# SparkFun_Mono_Audio_Amp-TPA2005D1.net
KiCad netlist of a schematic drawn in EAGLE
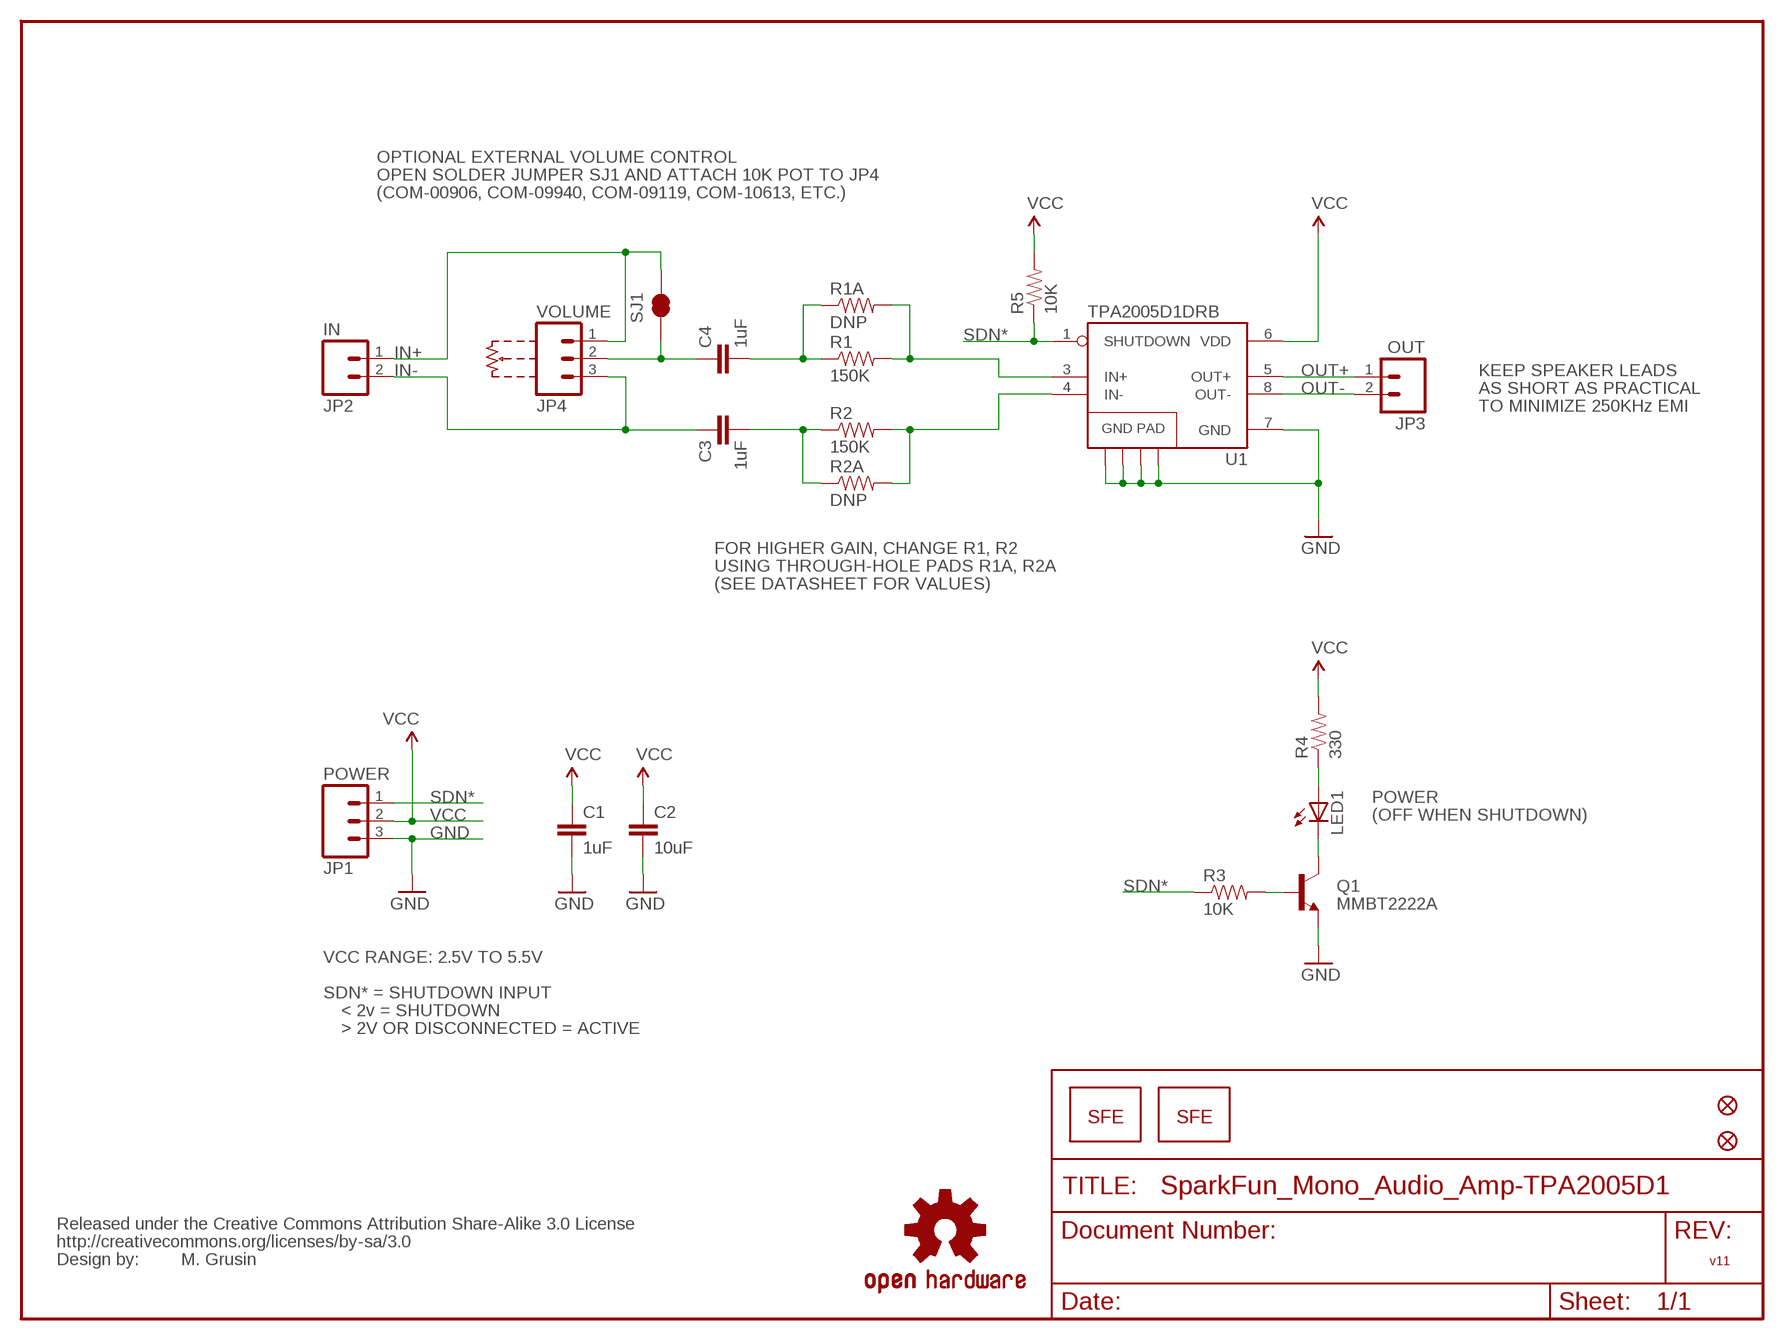
[diagram p0: schematic, sheet 1]

(export (version "E")
  (design (tool "Eeschema 10.0.6"))
  (components
    (comp (ref "C1")
      (value "1uF")
      (footprint "eagle-import:1206")
      (libsource (lib "eagle-import") (part "CAP1206"))
    )
    (comp (ref "C2")
      (value "10uF")
      (footprint "eagle-import:1206")
      (libsource (lib "eagle-import") (part "CAP1206"))
    )
    (comp (ref "C3")
      (value "1uF")
      (footprint "eagle-import:1206")
      (libsource (lib "eagle-import") (part "CAP1206"))
    )
    (comp (ref "C4")
      (value "1uF")
      (footprint "eagle-import:1206")
      (libsource (lib "eagle-import") (part "CAP1206"))
    )
    (comp (ref "JP1")
      (value "POWER")
      (footprint "eagle-import:1X03")
      (libsource (lib "eagle-import") (part "M03PTH"))
    )
    (comp (ref "JP2")
      (value "IN")
      (footprint "eagle-import:1X02")
      (libsource (lib "eagle-import") (part "M02PTH"))
    )
    (comp (ref "JP3")
      (value "OUT")
      (footprint "eagle-import:1X02")
      (libsource (lib "eagle-import") (part "M02PTH"))
    )
    (comp (ref "JP4")
      (value "VOLUME")
      (footprint "eagle-import:1X03")
      (libsource (lib "eagle-import") (part "M03PTH"))
    )
    (comp (ref "JP5")
      (value "FIDUCIALUFIDUCIAL")
      (footprint "eagle-import:MICRO-FIDUCIAL")
      (libsource (lib "eagle-import") (part "FIDUCIALUFIDUCIAL"))
    )
    (comp (ref "JP6")
      (value "FIDUCIALUFIDUCIAL")
      (footprint "eagle-import:MICRO-FIDUCIAL")
      (libsource (lib "eagle-import") (part "FIDUCIALUFIDUCIAL"))
    )
    (comp (ref "LED1")
      (value "LED0603")
      (footprint "eagle-import:LED-0603")
      (libsource (lib "eagle-import") (part "LED0603"))
    )
    (comp (ref "LOGO1")
      (value "LOGO-SFENW2")
      (footprint "eagle-import:SFE-NEW-WEB")
      (libsource (lib "eagle-import") (part "LOGO-SFENW2"))
    )
    (comp (ref "LOGO2")
      (value "LOGO-SFESK")
      (footprint "eagle-import:SFE-LOGO-FLAME")
      (libsource (lib "eagle-import") (part "LOGO-SFESK"))
    )
    (comp (ref "Q1")
      (value "MMBT2222A")
      (footprint "eagle-import:SOT23-3")
      (libsource (lib "eagle-import") (part "TRANSISTOR_NPNSOT23-3"))
    )
    (comp (ref "R1")
      (value "150K")
      (footprint "eagle-import:0603-RES")
      (libsource (lib "eagle-import") (part "RESISTOR0603-RES"))
    )
    (comp (ref "R1A")
      (value "DNP")
      (footprint "eagle-import:AXIAL-0.3")
      (libsource (lib "eagle-import") (part "RESISTORAXIAL-0.3"))
    )
    (comp (ref "R2")
      (value "150K")
      (footprint "eagle-import:0603-RES")
      (libsource (lib "eagle-import") (part "RESISTOR0603-RES"))
    )
    (comp (ref "R2A")
      (value "DNP")
      (footprint "eagle-import:AXIAL-0.3")
      (libsource (lib "eagle-import") (part "RESISTORAXIAL-0.3"))
    )
    (comp (ref "R3")
      (value "10K")
      (footprint "eagle-import:0603-RES")
      (libsource (lib "eagle-import") (part "RESISTOR0603-RES"))
    )
    (comp (ref "R4")
      (value "330")
      (footprint "eagle-import:0603-RES")
      (libsource (lib "eagle-import") (part "RESISTOR0603-RES"))
    )
    (comp (ref "R5")
      (value "10K")
      (footprint "eagle-import:0603-RES")
      (libsource (lib "eagle-import") (part "RESISTOR0603-RES"))
    )
    (comp (ref "SJ1")
      (value "SOLDERJUMPERNC2")
      (footprint "eagle-import:SJ_2S-NOTRACE")
      (libsource (lib "eagle-import") (part "SOLDERJUMPERNC2"))
    )
    (comp (ref "U$1")
      (value "CREATIVE_COMMONS")
      (footprint "eagle-import:CREATIVE_COMMONS")
      (libsource (lib "eagle-import") (part "CREATIVE_COMMONS"))
    )
    (comp (ref "U$2")
      (value "OSHW-LOGOS")
      (footprint "eagle-import:OSHW-LOGO-S")
      (libsource (lib "eagle-import") (part "OSHW-LOGOS"))
    )
    (comp (ref "U1")
      (value "TPA2005D1DRB")
      (footprint "eagle-import:QFN-8_PAD")
      (libsource (lib "eagle-import") (part "TPA2005D1DRB"))
    )
  )
  (nets
    (net (code "1") (name "/IN+") (class "Default")
      (node (ref "JP2") (pin "1") (pinfunction "1_1") (pintype "passive"))
      (node (ref "JP4") (pin "1") (pinfunction "1_1") (pintype "passive"))
      (node (ref "SJ1") (pin "2") (pinfunction "2_2") (pintype "passive"))
    )
    (net (code "2") (name "/IN-") (class "Default")
      (node (ref "C3") (pin "1") (pinfunction "1_1") (pintype "passive"))
      (node (ref "JP2") (pin "2") (pinfunction "2_2") (pintype "passive"))
      (node (ref "JP4") (pin "3") (pinfunction "3_3") (pintype "passive"))
    )
    (net (code "3") (name "/OUT+") (class "Default")
      (node (ref "JP3") (pin "1") (pinfunction "1_1") (pintype "passive"))
      (node (ref "U1") (pin "5") (pinfunction "OUT+_5") (pintype "bidirectional"))
    )
    (net (code "4") (name "/OUT-") (class "Default")
      (node (ref "JP3") (pin "2") (pinfunction "2_2") (pintype "passive"))
      (node (ref "U1") (pin "8") (pinfunction "OUT-_8") (pintype "bidirectional"))
    )
    (net (code "5") (name "/SDN*") (class "Default")
      (node (ref "JP1") (pin "1") (pinfunction "1_1") (pintype "passive"))
      (node (ref "R3") (pin "1") (pinfunction "1_1") (pintype "passive"))
      (node (ref "R5") (pin "1") (pinfunction "1_1") (pintype "passive"))
      (node (ref "U1") (pin "1") (pinfunction "SHUTDOWN_1") (pintype "input"))
    )
    (net (code "6") (name "GND") (class "Default")
      (node (ref "C1") (pin "2") (pinfunction "2_2") (pintype "passive"))
      (node (ref "C2") (pin "2") (pinfunction "2_2") (pintype "passive"))
      (node (ref "JP1") (pin "3") (pinfunction "3_3") (pintype "passive"))
      (node (ref "Q1") (pin "2") (pinfunction "E_2") (pintype "passive"))
      (node (ref "U1") (pin "10") (pinfunction "GND_10") (pintype "power_in"))
      (node (ref "U1") (pin "11") (pinfunction "GND_11") (pintype "power_in"))
      (node (ref "U1") (pin "12") (pinfunction "GND_12") (pintype "bidirectional"))
      (node (ref "U1") (pin "13") (pinfunction "GND_13") (pintype "bidirectional"))
      (node (ref "U1") (pin "7") (pinfunction "GND_7") (pintype "power_in"))
    )
    (net (code "7") (name "Net-(C4-Pad1)") (class "Default")
      (node (ref "C4") (pin "1") (pinfunction "1_1") (pintype "passive"))
      (node (ref "JP4") (pin "2") (pinfunction "2_2") (pintype "passive"))
      (node (ref "SJ1") (pin "1") (pinfunction "1_1") (pintype "passive"))
    )
    (net (code "8") (name "Net-(LED1-PadA)") (class "Default")
      (node (ref "LED1") (pin "A") (pinfunction "A_A") (pintype "passive"))
      (node (ref "R4") (pin "1") (pinfunction "1_1") (pintype "passive"))
    )
    (net (code "9") (name "Net-(Q1-B)") (class "Default")
      (node (ref "Q1") (pin "1") (pinfunction "B_1") (pintype "passive"))
      (node (ref "R3") (pin "2") (pinfunction "2_2") (pintype "passive"))
    )
    (net (code "10") (name "Net-(Q1-C)") (class "Default")
      (node (ref "LED1") (pin "C") (pinfunction "C_C") (pintype "passive"))
      (node (ref "Q1") (pin "3") (pinfunction "C_3") (pintype "passive"))
    )
    (net (code "11") (name "Net-(R1A-1)") (class "Default")
      (node (ref "C4") (pin "2") (pinfunction "2_2") (pintype "passive"))
      (node (ref "R1") (pin "1") (pinfunction "1_1") (pintype "passive"))
      (node (ref "R1A") (pin "P$1") (pinfunction "1_P$1") (pintype "passive"))
    )
    (net (code "12") (name "Net-(R1A-2)") (class "Default")
      (node (ref "R1") (pin "2") (pinfunction "2_2") (pintype "passive"))
      (node (ref "R1A") (pin "P$2") (pinfunction "2_P$2") (pintype "passive"))
      (node (ref "U1") (pin "3") (pinfunction "IN+_3") (pintype "bidirectional"))
    )
    (net (code "13") (name "Net-(R2A-1)") (class "Default")
      (node (ref "C3") (pin "2") (pinfunction "2_2") (pintype "passive"))
      (node (ref "R2") (pin "1") (pinfunction "1_1") (pintype "passive"))
      (node (ref "R2A") (pin "P$1") (pinfunction "1_P$1") (pintype "passive"))
    )
    (net (code "14") (name "Net-(R2A-2)") (class "Default")
      (node (ref "R2") (pin "2") (pinfunction "2_2") (pintype "passive"))
      (node (ref "R2A") (pin "P$2") (pinfunction "2_P$2") (pintype "passive"))
      (node (ref "U1") (pin "4") (pinfunction "IN-_4") (pintype "bidirectional"))
    )
    (net (code "15") (name "VCC") (class "Default")
      (node (ref "C1") (pin "1") (pinfunction "1_1") (pintype "passive"))
      (node (ref "C2") (pin "1") (pinfunction "1_1") (pintype "passive"))
      (node (ref "JP1") (pin "2") (pinfunction "2_2") (pintype "passive"))
      (node (ref "R4") (pin "2") (pinfunction "2_2") (pintype "passive"))
      (node (ref "R5") (pin "2") (pinfunction "2_2") (pintype "passive"))
      (node (ref "U1") (pin "6") (pinfunction "VDD_6") (pintype "power_in"))
    )
  )
)
